# Keithley_2000_Omron_SCAN_V1_0.net
KiCad netlist of a schematic drawn in EasyEDA Pro
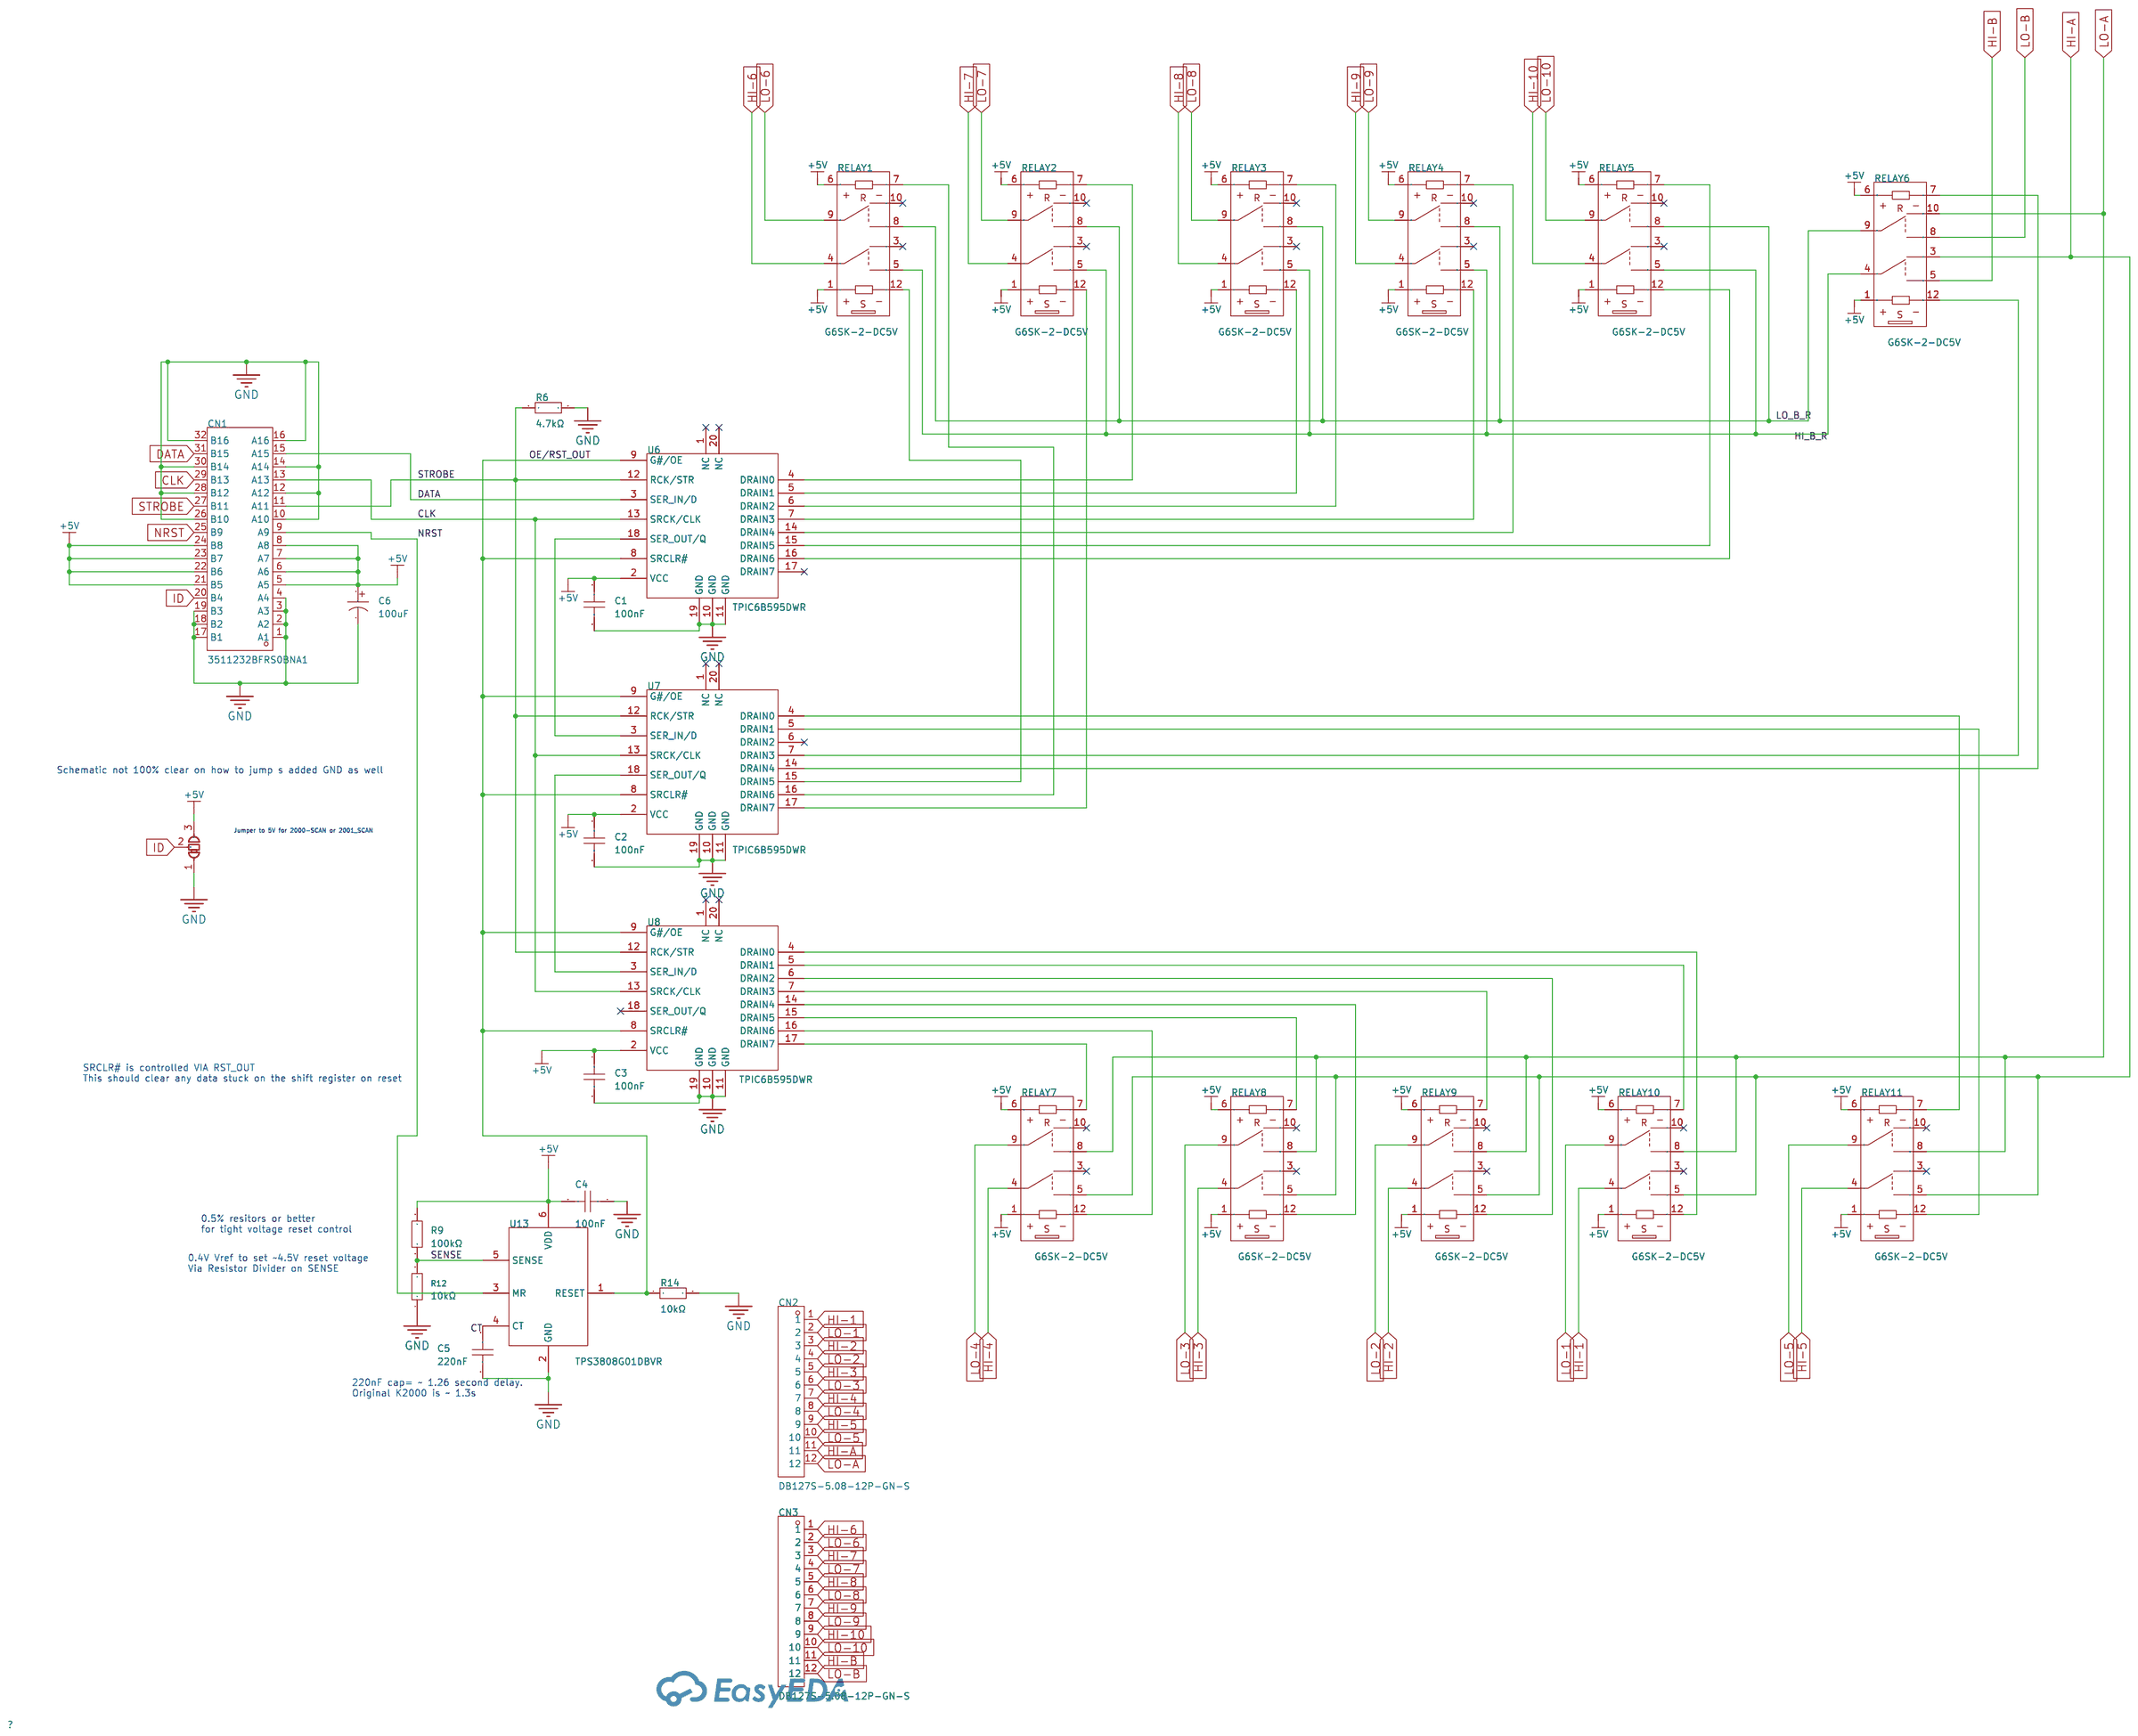
[diagram p0: schematic sheet]

(export (version "E")
  (design (tool "Eeschema 10.0.6"))
  (components
    (comp (ref "C1")
      (value "100nF")
      (description "Capacitance:100nF Tolerance:±10% Tolerance:±10% Voltage Rating:50V Temperature Coefficient:X7R")
      (fields
        (field (name "Manufacturer Part") "CL10B104KB8NNNC")
        (field (name "Manufacturer") "SAMSUNG(三星)")
      )
      (libsource (lib "easyedapro") (part "CAP"))
    )
    (comp (ref "C2")
      (value "100nF")
      (description "Capacitance:100nF Tolerance:±10% Tolerance:±10% Voltage Rating:50V Temperature Coefficient:X7R")
      (fields
        (field (name "Manufacturer Part") "CL10B104KB8NNNC")
        (field (name "Manufacturer") "SAMSUNG(三星)")
      )
      (libsource (lib "easyedapro") (part "CAP"))
    )
    (comp (ref "C3")
      (value "100nF")
      (description "Capacitance:100nF Tolerance:±10% Tolerance:±10% Voltage Rating:50V Temperature Coefficient:X7R")
      (fields
        (field (name "Manufacturer Part") "CL10B104KB8NNNC")
        (field (name "Manufacturer") "SAMSUNG(三星)")
      )
      (libsource (lib "easyedapro") (part "CAP"))
    )
    (comp (ref "C4")
      (value "100nF")
      (description "Capacitance:100nF Tolerance:±10% Tolerance:±10% Voltage Rating:50V Temperature Coefficient:X7R")
      (fields
        (field (name "Manufacturer Part") "CL10B104KB8NNNC")
        (field (name "Manufacturer") "SAMSUNG(三星)")
      )
      (libsource (lib "easyedapro") (part "CAP"))
    )
    (comp (ref "C5")
      (value "220nF")
      (description "Capacitance:220nF Tolerance:±10% Tolerance:±10% Voltage Rating:25V Temperature Coefficient:X7R")
      (fields
        (field (name "Manufacturer Part") "CL10B224KA8NNNC")
        (field (name "Manufacturer") "SAMSUNG(三星)")
      )
      (libsource (lib "easyedapro") (part "CAP"))
    )
    (comp (ref "C6")
      (value "100uF")
      (footprint "easyedapro:CAP-TH_BD8.0-P3.50-D0.6-FD")
      (fields (field (name "Manufacturer Part") "ERJ1HM101F12OT") (field (name "Manufacturer") "AISHI(艾华集团)"))
      (libsource (lib "easyedapro") (part "ERJ1HM101F12OT"))
    )
    (comp (ref "CN1")
      (value "3511232BFRS0BNA1")
      (footprint "easyedapro:CONN-TH_3511232BFRS0BNA1")
      (fields (field (name "Manufacturer") "JILN(锦凌)"))
      (libsource (lib "easyedapro") (part "3511232BFRS0BNA1"))
    )
    (comp (ref "CN2")
      (value "DB127S-5.08-12P-GN-S")
      (footprint "easyedapro:CONN-TH_12P-P5.08_DB127S-5.08-12P-GN-S")
      (fields (field (name "Manufacturer") "DORABO(地博电气)"))
      (libsource (lib "easyedapro") (part "DB127S-5.08-12P-GN-S"))
    )
    (comp (ref "CN3")
      (value "DB127S-5.08-12P-GN-S")
      (footprint "easyedapro:CONN-TH_12P-P5.08_DB127S-5.08-12P-GN-S")
      (fields (field (name "Manufacturer") "DORABO(地博电气)"))
      (libsource (lib "easyedapro") (part "DB127S-5.08-12P-GN-S"))
    )
    (comp (ref "JP1")
      (value "SolderJumper_3_Bridged12")
      (footprint "easyedapro:Jumper:SolderJumper-3_P1.3mm_Bridged12_Pad1.0x1.5mm_NumberLabels")
      (description "3-pole Solder Jumper, pins 1+2 closed/bridged")
      (libsource (lib "easyedapro") (part "Jumper_SolderJumper_3_Bridged12"))
    )
    (comp (ref "R6")
      (value "4.7kΩ")
      (fields (field (name "Manufacturer Part") "RC0603FR-074K7L") (field (name "Manufacturer") "YAGEO(国巨)"))
      (libsource (lib "easyedapro") (part "Res"))
    )
    (comp (ref "R9")
      (value "100kΩ")
      (footprint "easyedapro:R0603")
      (fields (field (name "Manufacturer Part") "AR03DTCX1003") (field (name "Manufacturer") "Viking(光颉)"))
      (libsource (lib "easyedapro") (part "AR03DTCX1003"))
    )
    (comp (ref "R12")
      (value "10kΩ")
      (footprint "easyedapro:R0603")
      (fields
        (field (name "Manufacturer Part") "0603WAD1002T5E")
        (field (name "Manufacturer") "UNI-ROYAL(厚声)")
      )
      (libsource (lib "easyedapro") (part "0603WAD1002T5E"))
    )
    (comp (ref "R14")
      (value "10kΩ")
      (fields (field (name "Manufacturer Part") "RC0603FR-0710KL") (field (name "Manufacturer") "YAGEO(国巨)"))
      (libsource (lib "easyedapro") (part "Res"))
    )
    (comp (ref "RELAY1")
      (value "G6SK-2-DC5V")
      (footprint "easyedapro:RELAY-TH_G6SK-2-XXX")
      (fields (field (name "Manufacturer") "OMRON(欧姆龙)"))
      (libsource (lib "easyedapro") (part "G6SK-2-DC5V"))
    )
    (comp (ref "RELAY2")
      (value "G6SK-2-DC5V")
      (footprint "easyedapro:RELAY-TH_G6SK-2-XXX")
      (fields (field (name "Manufacturer") "OMRON(欧姆龙)"))
      (libsource (lib "easyedapro") (part "G6SK-2-DC5V"))
    )
    (comp (ref "RELAY3")
      (value "G6SK-2-DC5V")
      (footprint "easyedapro:RELAY-TH_G6SK-2-XXX")
      (fields (field (name "Manufacturer") "OMRON(欧姆龙)"))
      (libsource (lib "easyedapro") (part "G6SK-2-DC5V"))
    )
    (comp (ref "RELAY4")
      (value "G6SK-2-DC5V")
      (footprint "easyedapro:RELAY-TH_G6SK-2-XXX")
      (fields (field (name "Manufacturer") "OMRON(欧姆龙)"))
      (libsource (lib "easyedapro") (part "G6SK-2-DC5V"))
    )
    (comp (ref "RELAY5")
      (value "G6SK-2-DC5V")
      (footprint "easyedapro:RELAY-TH_G6SK-2-XXX")
      (fields (field (name "Manufacturer") "OMRON(欧姆龙)"))
      (libsource (lib "easyedapro") (part "G6SK-2-DC5V"))
    )
    (comp (ref "RELAY6")
      (value "G6SK-2-DC5V")
      (footprint "easyedapro:RELAY-TH_G6SK-2-XXX")
      (fields (field (name "Manufacturer") "OMRON(欧姆龙)"))
      (libsource (lib "easyedapro") (part "G6SK-2-DC5V"))
    )
    (comp (ref "RELAY7")
      (value "G6SK-2-DC5V")
      (footprint "easyedapro:RELAY-TH_G6SK-2-XXX")
      (fields (field (name "Manufacturer") "OMRON(欧姆龙)"))
      (libsource (lib "easyedapro") (part "G6SK-2-DC5V"))
    )
    (comp (ref "RELAY8")
      (value "G6SK-2-DC5V")
      (footprint "easyedapro:RELAY-TH_G6SK-2-XXX")
      (fields (field (name "Manufacturer") "OMRON(欧姆龙)"))
      (libsource (lib "easyedapro") (part "G6SK-2-DC5V"))
    )
    (comp (ref "RELAY9")
      (value "G6SK-2-DC5V")
      (footprint "easyedapro:RELAY-TH_G6SK-2-XXX")
      (fields (field (name "Manufacturer") "OMRON(欧姆龙)"))
      (libsource (lib "easyedapro") (part "G6SK-2-DC5V"))
    )
    (comp (ref "RELAY10")
      (value "G6SK-2-DC5V")
      (footprint "easyedapro:RELAY-TH_G6SK-2-XXX")
      (fields (field (name "Manufacturer") "OMRON(欧姆龙)"))
      (libsource (lib "easyedapro") (part "G6SK-2-DC5V"))
    )
    (comp (ref "RELAY11")
      (value "G6SK-2-DC5V")
      (footprint "easyedapro:RELAY-TH_G6SK-2-XXX")
      (fields (field (name "Manufacturer") "OMRON(欧姆龙)"))
      (libsource (lib "easyedapro") (part "G6SK-2-DC5V"))
    )
    (comp (ref "U6")
      (value "TPIC6B595DWR")
      (footprint "easyedapro:SOIC-20_L13.0-W7.6-P1.27-LS10.3-BL")
      (fields (field (name "Manufacturer") "TI(德州仪器)"))
      (libsource (lib "easyedapro") (part "TPIC6B595DWR"))
    )
    (comp (ref "U7")
      (value "TPIC6B595DWR")
      (footprint "easyedapro:SOIC-20_L13.0-W7.6-P1.27-LS10.3-BL")
      (fields (field (name "Manufacturer") "TI(德州仪器)"))
      (libsource (lib "easyedapro") (part "TPIC6B595DWR"))
    )
    (comp (ref "U8")
      (value "TPIC6B595DWR")
      (footprint "easyedapro:SOIC-20_L13.0-W7.6-P1.27-LS10.3-BL")
      (fields (field (name "Manufacturer") "TI(德州仪器)"))
      (libsource (lib "easyedapro") (part "TPIC6B595DWR"))
    )
    (comp (ref "U13")
      (value "TPS3808G01DBVR")
      (footprint "easyedapro:SOT-23-6_L2.9-W1.6-P0.95-LS2.8-BR")
      (fields (field (name "Manufacturer") "TI(德州仪器)"))
      (libsource (lib "easyedapro") (part "TPS3808G01DBVR"))
    )
  )
  (nets
    (net (code "1") (name "+5V") (class "Default")
      (node (ref "C1") (pin "1") (pinfunction "1_1") (pintype "input"))
      (node (ref "C2") (pin "1") (pinfunction "1_1") (pintype "input"))
      (node (ref "C3") (pin "1") (pinfunction "1_1") (pintype "input"))
      (node (ref "C4") (pin "2") (pinfunction "2_2") (pintype "input"))
      (node (ref "C6") (pin "1") (pinfunction "1_1") (pintype "input"))
      (node (ref "CN1") (pin "21") (pinfunction "B5_21") (pintype "unspecified"))
      (node (ref "CN1") (pin "22") (pinfunction "B6_22") (pintype "unspecified"))
      (node (ref "CN1") (pin "23") (pinfunction "B7_23") (pintype "unspecified"))
      (node (ref "CN1") (pin "24") (pinfunction "B8_24") (pintype "unspecified"))
      (node (ref "CN1") (pin "5") (pinfunction "A5_5") (pintype "unspecified"))
      (node (ref "CN1") (pin "6") (pinfunction "A6_6") (pintype "unspecified"))
      (node (ref "CN1") (pin "7") (pinfunction "A7_7") (pintype "unspecified"))
      (node (ref "CN1") (pin "8") (pinfunction "A8_8") (pintype "unspecified"))
      (node (ref "JP1") (pin "3") (pinfunction "B_3") (pintype "unspecified"))
      (node (ref "R9") (pin "2") (pinfunction "2_2") (pintype "unspecified"))
      (node (ref "RELAY1") (pin "1") (pinfunction "1_1") (pintype "unspecified"))
      (node (ref "RELAY1") (pin "6") (pinfunction "6_6") (pintype "unspecified"))
      (node (ref "RELAY10") (pin "1") (pinfunction "1_1") (pintype "unspecified"))
      (node (ref "RELAY10") (pin "6") (pinfunction "6_6") (pintype "unspecified"))
      (node (ref "RELAY11") (pin "1") (pinfunction "1_1") (pintype "unspecified"))
      (node (ref "RELAY11") (pin "6") (pinfunction "6_6") (pintype "unspecified"))
      (node (ref "RELAY2") (pin "1") (pinfunction "1_1") (pintype "unspecified"))
      (node (ref "RELAY2") (pin "6") (pinfunction "6_6") (pintype "unspecified"))
      (node (ref "RELAY3") (pin "1") (pinfunction "1_1") (pintype "unspecified"))
      (node (ref "RELAY3") (pin "6") (pinfunction "6_6") (pintype "unspecified"))
      (node (ref "RELAY4") (pin "1") (pinfunction "1_1") (pintype "unspecified"))
      (node (ref "RELAY4") (pin "6") (pinfunction "6_6") (pintype "unspecified"))
      (node (ref "RELAY5") (pin "1") (pinfunction "1_1") (pintype "unspecified"))
      (node (ref "RELAY5") (pin "6") (pinfunction "6_6") (pintype "unspecified"))
      (node (ref "RELAY6") (pin "1") (pinfunction "1_1") (pintype "unspecified"))
      (node (ref "RELAY6") (pin "6") (pinfunction "6_6") (pintype "unspecified"))
      (node (ref "RELAY7") (pin "1") (pinfunction "1_1") (pintype "unspecified"))
      (node (ref "RELAY7") (pin "6") (pinfunction "6_6") (pintype "unspecified"))
      (node (ref "RELAY8") (pin "1") (pinfunction "1_1") (pintype "unspecified"))
      (node (ref "RELAY8") (pin "6") (pinfunction "6_6") (pintype "unspecified"))
      (node (ref "RELAY9") (pin "1") (pinfunction "1_1") (pintype "unspecified"))
      (node (ref "RELAY9") (pin "6") (pinfunction "6_6") (pintype "unspecified"))
      (node (ref "U13") (pin "6") (pinfunction "VDD_6") (pintype "unspecified"))
      (node (ref "U6") (pin "2") (pinfunction "VCC_2") (pintype "unspecified"))
      (node (ref "U7") (pin "2") (pinfunction "VCC_2") (pintype "unspecified"))
      (node (ref "U8") (pin "2") (pinfunction "VCC_2") (pintype "unspecified"))
    )
    (net (code "2") (name "/CT") (class "Default")
      (node (ref "C5") (pin "1") (pinfunction "1_1") (pintype "input"))
      (node (ref "U13") (pin "4") (pinfunction "CT_4") (pintype "unspecified"))
    )
    (net (code "3") (name "/HI_B_R") (class "Default")
      (node (ref "RELAY1") (pin "5") (pinfunction "5_5") (pintype "unspecified"))
      (node (ref "RELAY2") (pin "5") (pinfunction "5_5") (pintype "unspecified"))
      (node (ref "RELAY3") (pin "5") (pinfunction "5_5") (pintype "unspecified"))
      (node (ref "RELAY4") (pin "5") (pinfunction "5_5") (pintype "unspecified"))
      (node (ref "RELAY5") (pin "5") (pinfunction "5_5") (pintype "unspecified"))
      (node (ref "RELAY6") (pin "4") (pinfunction "4_4") (pintype "unspecified"))
    )
    (net (code "4") (name "/LO_B_R") (class "Default")
      (node (ref "RELAY1") (pin "8") (pinfunction "8_8") (pintype "unspecified"))
      (node (ref "RELAY2") (pin "8") (pinfunction "8_8") (pintype "unspecified"))
      (node (ref "RELAY3") (pin "8") (pinfunction "8_8") (pintype "unspecified"))
      (node (ref "RELAY4") (pin "8") (pinfunction "8_8") (pintype "unspecified"))
      (node (ref "RELAY5") (pin "8") (pinfunction "8_8") (pintype "unspecified"))
      (node (ref "RELAY6") (pin "9") (pinfunction "9_9") (pintype "unspecified"))
    )
    (net (code "5") (name "/OE{slash}RST_OUT") (class "Default")
      (node (ref "R14") (pin "1") (pinfunction "1_1") (pintype "input"))
      (node (ref "U13") (pin "1") (pinfunction "RESET_1") (pintype "unspecified"))
      (node (ref "U6") (pin "8") (pinfunction "SRCLR#_8") (pintype "unspecified"))
      (node (ref "U6") (pin "9") (pinfunction "G#/OE_9") (pintype "unspecified"))
      (node (ref "U7") (pin "8") (pinfunction "SRCLR#_8") (pintype "unspecified"))
      (node (ref "U7") (pin "9") (pinfunction "G#/OE_9") (pintype "unspecified"))
      (node (ref "U8") (pin "8") (pinfunction "SRCLR#_8") (pintype "unspecified"))
      (node (ref "U8") (pin "9") (pinfunction "G#/OE_9") (pintype "unspecified"))
    )
    (net (code "6") (name "/SENSE") (class "Default")
      (node (ref "R12") (pin "2") (pinfunction "2_2") (pintype "input"))
      (node (ref "R9") (pin "1") (pinfunction "1_1") (pintype "unspecified"))
      (node (ref "U13") (pin "5") (pinfunction "SENSE_5") (pintype "unspecified"))
    )
    (net (code "7") (name "CLK") (class "Default")
      (node (ref "CN1") (pin "13") (pinfunction "A13_13") (pintype "unspecified"))
      (node (ref "CN1") (pin "29") (pinfunction "B13_29") (pintype "unspecified"))
      (node (ref "U6") (pin "13") (pinfunction "SRCK/CLK_13") (pintype "unspecified"))
      (node (ref "U7") (pin "13") (pinfunction "SRCK/CLK_13") (pintype "unspecified"))
      (node (ref "U8") (pin "13") (pinfunction "SRCK/CLK_13") (pintype "unspecified"))
    )
    (net (code "8") (name "DATA") (class "Default")
      (node (ref "CN1") (pin "15") (pinfunction "A15_15") (pintype "unspecified"))
      (node (ref "CN1") (pin "31") (pinfunction "B15_31") (pintype "unspecified"))
      (node (ref "U6") (pin "3") (pinfunction "SER_IN/D_3") (pintype "unspecified"))
    )
    (net (code "9") (name "GND") (class "Default")
      (node (ref "C1") (pin "2") (pinfunction "2_2") (pintype "input"))
      (node (ref "C2") (pin "2") (pinfunction "2_2") (pintype "input"))
      (node (ref "C3") (pin "2") (pinfunction "2_2") (pintype "input"))
      (node (ref "C4") (pin "1") (pinfunction "1_1") (pintype "input"))
      (node (ref "C5") (pin "2") (pinfunction "2_2") (pintype "input"))
      (node (ref "C6") (pin "2") (pinfunction "2_2") (pintype "input"))
      (node (ref "CN1") (pin "1") (pinfunction "A1_1") (pintype "unspecified"))
      (node (ref "CN1") (pin "10") (pinfunction "A10_10") (pintype "unspecified"))
      (node (ref "CN1") (pin "12") (pinfunction "A12_12") (pintype "unspecified"))
      (node (ref "CN1") (pin "14") (pinfunction "A14_14") (pintype "unspecified"))
      (node (ref "CN1") (pin "16") (pinfunction "A16_16") (pintype "unspecified"))
      (node (ref "CN1") (pin "17") (pinfunction "B1_17") (pintype "unspecified"))
      (node (ref "CN1") (pin "18") (pinfunction "B2_18") (pintype "unspecified"))
      (node (ref "CN1") (pin "19") (pinfunction "B3_19") (pintype "unspecified"))
      (node (ref "CN1") (pin "2") (pinfunction "A2_2") (pintype "unspecified"))
      (node (ref "CN1") (pin "26") (pinfunction "B10_26") (pintype "unspecified"))
      (node (ref "CN1") (pin "28") (pinfunction "B12_28") (pintype "unspecified"))
      (node (ref "CN1") (pin "3") (pinfunction "A3_3") (pintype "unspecified"))
      (node (ref "CN1") (pin "30") (pinfunction "B14_30") (pintype "unspecified"))
      (node (ref "CN1") (pin "32") (pinfunction "B16_32") (pintype "unspecified"))
      (node (ref "CN1") (pin "4") (pinfunction "A4_4") (pintype "unspecified"))
      (node (ref "JP1") (pin "1") (pinfunction "A_1") (pintype "unspecified"))
      (node (ref "R12") (pin "1") (pinfunction "1_1") (pintype "input"))
      (node (ref "R14") (pin "2") (pinfunction "2_2") (pintype "input"))
      (node (ref "R6") (pin "2") (pinfunction "2_2") (pintype "input"))
      (node (ref "U13") (pin "2") (pinfunction "GND_2") (pintype "unspecified"))
      (node (ref "U6") (pin "10") (pinfunction "GND_10") (pintype "unspecified"))
      (node (ref "U6") (pin "11") (pinfunction "GND_11") (pintype "unspecified"))
      (node (ref "U6") (pin "19") (pinfunction "GND_19") (pintype "unspecified"))
      (node (ref "U7") (pin "10") (pinfunction "GND_10") (pintype "unspecified"))
      (node (ref "U7") (pin "11") (pinfunction "GND_11") (pintype "unspecified"))
      (node (ref "U7") (pin "19") (pinfunction "GND_19") (pintype "unspecified"))
      (node (ref "U8") (pin "10") (pinfunction "GND_10") (pintype "unspecified"))
      (node (ref "U8") (pin "11") (pinfunction "GND_11") (pintype "unspecified"))
      (node (ref "U8") (pin "19") (pinfunction "GND_19") (pintype "unspecified"))
    )
    (net (code "10") (name "HI-1") (class "Default")
      (node (ref "CN2") (pin "1") (pinfunction "1_1") (pintype "unspecified"))
      (node (ref "RELAY10") (pin "4") (pinfunction "4_4") (pintype "unspecified"))
    )
    (net (code "11") (name "HI-2") (class "Default")
      (node (ref "CN2") (pin "3") (pinfunction "3_3") (pintype "unspecified"))
      (node (ref "RELAY9") (pin "4") (pinfunction "4_4") (pintype "unspecified"))
    )
    (net (code "12") (name "HI-3") (class "Default")
      (node (ref "CN2") (pin "5") (pinfunction "5_5") (pintype "unspecified"))
      (node (ref "RELAY8") (pin "4") (pinfunction "4_4") (pintype "unspecified"))
    )
    (net (code "13") (name "HI-4") (class "Default")
      (node (ref "CN2") (pin "7") (pinfunction "7_7") (pintype "unspecified"))
      (node (ref "RELAY7") (pin "4") (pinfunction "4_4") (pintype "unspecified"))
    )
    (net (code "14") (name "HI-5") (class "Default")
      (node (ref "CN2") (pin "9") (pinfunction "9_9") (pintype "unspecified"))
      (node (ref "RELAY11") (pin "4") (pinfunction "4_4") (pintype "unspecified"))
    )
    (net (code "15") (name "HI-6") (class "Default")
      (node (ref "CN3") (pin "1") (pinfunction "1_1") (pintype "unspecified"))
      (node (ref "RELAY1") (pin "4") (pinfunction "4_4") (pintype "unspecified"))
    )
    (net (code "16") (name "HI-7") (class "Default")
      (node (ref "CN3") (pin "3") (pinfunction "3_3") (pintype "unspecified"))
      (node (ref "RELAY2") (pin "4") (pinfunction "4_4") (pintype "unspecified"))
    )
    (net (code "17") (name "HI-8") (class "Default")
      (node (ref "CN3") (pin "5") (pinfunction "5_5") (pintype "unspecified"))
      (node (ref "RELAY3") (pin "4") (pinfunction "4_4") (pintype "unspecified"))
    )
    (net (code "18") (name "HI-9") (class "Default")
      (node (ref "CN3") (pin "7") (pinfunction "7_7") (pintype "unspecified"))
      (node (ref "RELAY4") (pin "4") (pinfunction "4_4") (pintype "unspecified"))
    )
    (net (code "19") (name "HI-10") (class "Default")
      (node (ref "CN3") (pin "9") (pinfunction "9_9") (pintype "unspecified"))
      (node (ref "RELAY5") (pin "4") (pinfunction "4_4") (pintype "unspecified"))
    )
    (net (code "20") (name "HI-A") (class "Default")
      (node (ref "CN2") (pin "11") (pinfunction "11_11") (pintype "unspecified"))
      (node (ref "RELAY10") (pin "5") (pinfunction "5_5") (pintype "unspecified"))
      (node (ref "RELAY11") (pin "5") (pinfunction "5_5") (pintype "unspecified"))
      (node (ref "RELAY6") (pin "3") (pinfunction "3_3") (pintype "unspecified"))
      (node (ref "RELAY7") (pin "5") (pinfunction "5_5") (pintype "unspecified"))
      (node (ref "RELAY8") (pin "5") (pinfunction "5_5") (pintype "unspecified"))
      (node (ref "RELAY9") (pin "5") (pinfunction "5_5") (pintype "unspecified"))
    )
    (net (code "21") (name "HI-B") (class "Default")
      (node (ref "CN3") (pin "11") (pinfunction "11_11") (pintype "unspecified"))
      (node (ref "RELAY6") (pin "5") (pinfunction "5_5") (pintype "unspecified"))
    )
    (net (code "22") (name "ID") (class "Default")
      (node (ref "CN1") (pin "20") (pinfunction "B4_20") (pintype "unspecified"))
      (node (ref "JP1") (pin "2") (pinfunction "C_2") (pintype "unspecified"))
    )
    (net (code "23") (name "LO-1") (class "Default")
      (node (ref "CN2") (pin "2") (pinfunction "2_2") (pintype "unspecified"))
      (node (ref "RELAY10") (pin "9") (pinfunction "9_9") (pintype "unspecified"))
    )
    (net (code "24") (name "LO-2") (class "Default")
      (node (ref "CN2") (pin "4") (pinfunction "4_4") (pintype "unspecified"))
      (node (ref "RELAY9") (pin "9") (pinfunction "9_9") (pintype "unspecified"))
    )
    (net (code "25") (name "LO-3") (class "Default")
      (node (ref "CN2") (pin "6") (pinfunction "6_6") (pintype "unspecified"))
      (node (ref "RELAY8") (pin "9") (pinfunction "9_9") (pintype "unspecified"))
    )
    (net (code "26") (name "LO-4") (class "Default")
      (node (ref "CN2") (pin "8") (pinfunction "8_8") (pintype "unspecified"))
      (node (ref "RELAY7") (pin "9") (pinfunction "9_9") (pintype "unspecified"))
    )
    (net (code "27") (name "LO-5") (class "Default")
      (node (ref "CN2") (pin "10") (pinfunction "10_10") (pintype "unspecified"))
      (node (ref "RELAY11") (pin "9") (pinfunction "9_9") (pintype "unspecified"))
    )
    (net (code "28") (name "LO-6") (class "Default")
      (node (ref "CN3") (pin "2") (pinfunction "2_2") (pintype "unspecified"))
      (node (ref "RELAY1") (pin "9") (pinfunction "9_9") (pintype "unspecified"))
    )
    (net (code "29") (name "LO-7") (class "Default")
      (node (ref "CN3") (pin "4") (pinfunction "4_4") (pintype "unspecified"))
      (node (ref "RELAY2") (pin "9") (pinfunction "9_9") (pintype "unspecified"))
    )
    (net (code "30") (name "LO-8") (class "Default")
      (node (ref "CN3") (pin "6") (pinfunction "6_6") (pintype "unspecified"))
      (node (ref "RELAY3") (pin "9") (pinfunction "9_9") (pintype "unspecified"))
    )
    (net (code "31") (name "LO-9") (class "Default")
      (node (ref "CN3") (pin "8") (pinfunction "8_8") (pintype "unspecified"))
      (node (ref "RELAY4") (pin "9") (pinfunction "9_9") (pintype "unspecified"))
    )
    (net (code "32") (name "LO-10") (class "Default")
      (node (ref "CN3") (pin "10") (pinfunction "10_10") (pintype "unspecified"))
      (node (ref "RELAY5") (pin "9") (pinfunction "9_9") (pintype "unspecified"))
    )
    (net (code "33") (name "LO-A") (class "Default")
      (node (ref "CN2") (pin "12") (pinfunction "12_12") (pintype "unspecified"))
      (node (ref "RELAY10") (pin "8") (pinfunction "8_8") (pintype "unspecified"))
      (node (ref "RELAY11") (pin "8") (pinfunction "8_8") (pintype "unspecified"))
      (node (ref "RELAY6") (pin "10") (pinfunction "10_10") (pintype "unspecified"))
      (node (ref "RELAY7") (pin "8") (pinfunction "8_8") (pintype "unspecified"))
      (node (ref "RELAY8") (pin "8") (pinfunction "8_8") (pintype "unspecified"))
      (node (ref "RELAY9") (pin "8") (pinfunction "8_8") (pintype "unspecified"))
    )
    (net (code "34") (name "LO-B") (class "Default")
      (node (ref "CN3") (pin "12") (pinfunction "12_12") (pintype "unspecified"))
      (node (ref "RELAY6") (pin "8") (pinfunction "8_8") (pintype "unspecified"))
    )
    (net (code "35") (name "NRST") (class "Default")
      (node (ref "CN1") (pin "25") (pinfunction "B9_25") (pintype "unspecified"))
      (node (ref "CN1") (pin "9") (pinfunction "A9_9") (pintype "unspecified"))
      (node (ref "U13") (pin "3") (pinfunction "MR_3") (pintype "unspecified"))
    )
    (net (code "36") (name "Net-(U6-DRAIN0)") (class "Default")
      (node (ref "RELAY2") (pin "7") (pinfunction "7_7") (pintype "unspecified"))
      (node (ref "U6") (pin "4") (pinfunction "DRAIN0_4") (pintype "unspecified"))
    )
    (net (code "37") (name "Net-(U6-DRAIN1)") (class "Default")
      (node (ref "RELAY3") (pin "12") (pinfunction "12_12") (pintype "unspecified"))
      (node (ref "U6") (pin "5") (pinfunction "DRAIN1_5") (pintype "unspecified"))
    )
    (net (code "38") (name "Net-(U6-DRAIN2)") (class "Default")
      (node (ref "RELAY3") (pin "7") (pinfunction "7_7") (pintype "unspecified"))
      (node (ref "U6") (pin "6") (pinfunction "DRAIN2_6") (pintype "unspecified"))
    )
    (net (code "39") (name "Net-(U6-DRAIN3)") (class "Default")
      (node (ref "RELAY4") (pin "12") (pinfunction "12_12") (pintype "unspecified"))
      (node (ref "U6") (pin "7") (pinfunction "DRAIN3_7") (pintype "unspecified"))
    )
    (net (code "40") (name "Net-(U6-DRAIN4)") (class "Default")
      (node (ref "RELAY4") (pin "7") (pinfunction "7_7") (pintype "unspecified"))
      (node (ref "U6") (pin "14") (pinfunction "DRAIN4_14") (pintype "unspecified"))
    )
    (net (code "41") (name "Net-(U6-DRAIN5)") (class "Default")
      (node (ref "RELAY5") (pin "7") (pinfunction "7_7") (pintype "unspecified"))
      (node (ref "U6") (pin "15") (pinfunction "DRAIN5_15") (pintype "unspecified"))
    )
    (net (code "42") (name "Net-(U6-DRAIN6)") (class "Default")
      (node (ref "RELAY5") (pin "12") (pinfunction "12_12") (pintype "unspecified"))
      (node (ref "U6") (pin "16") (pinfunction "DRAIN6_16") (pintype "unspecified"))
    )
    (net (code "43") (name "Net-(U6-SER_OUT{slash}Q)") (class "Default")
      (node (ref "U6") (pin "18") (pinfunction "SER_OUT/Q_18") (pintype "unspecified"))
      (node (ref "U7") (pin "3") (pinfunction "SER_IN/D_3") (pintype "unspecified"))
    )
    (net (code "44") (name "Net-(U7-DRAIN0)") (class "Default")
      (node (ref "RELAY11") (pin "7") (pinfunction "7_7") (pintype "unspecified"))
      (node (ref "U7") (pin "4") (pinfunction "DRAIN0_4") (pintype "unspecified"))
    )
    (net (code "45") (name "Net-(U7-DRAIN1)") (class "Default")
      (node (ref "RELAY11") (pin "12") (pinfunction "12_12") (pintype "unspecified"))
      (node (ref "U7") (pin "5") (pinfunction "DRAIN1_5") (pintype "unspecified"))
    )
    (net (code "46") (name "Net-(U7-DRAIN3)") (class "Default")
      (node (ref "RELAY6") (pin "12") (pinfunction "12_12") (pintype "unspecified"))
      (node (ref "U7") (pin "7") (pinfunction "DRAIN3_7") (pintype "unspecified"))
    )
    (net (code "47") (name "Net-(U7-DRAIN4)") (class "Default")
      (node (ref "RELAY6") (pin "7") (pinfunction "7_7") (pintype "unspecified"))
      (node (ref "U7") (pin "14") (pinfunction "DRAIN4_14") (pintype "unspecified"))
    )
    (net (code "48") (name "Net-(U7-DRAIN5)") (class "Default")
      (node (ref "RELAY1") (pin "12") (pinfunction "12_12") (pintype "unspecified"))
      (node (ref "U7") (pin "15") (pinfunction "DRAIN5_15") (pintype "unspecified"))
    )
    (net (code "49") (name "Net-(U7-DRAIN6)") (class "Default")
      (node (ref "RELAY1") (pin "7") (pinfunction "7_7") (pintype "unspecified"))
      (node (ref "U7") (pin "16") (pinfunction "DRAIN6_16") (pintype "unspecified"))
    )
    (net (code "50") (name "Net-(U7-DRAIN7)") (class "Default")
      (node (ref "RELAY2") (pin "12") (pinfunction "12_12") (pintype "unspecified"))
      (node (ref "U7") (pin "17") (pinfunction "DRAIN7_17") (pintype "unspecified"))
    )
    (net (code "51") (name "Net-(U7-SER_OUT{slash}Q)") (class "Default")
      (node (ref "U7") (pin "18") (pinfunction "SER_OUT/Q_18") (pintype "unspecified"))
      (node (ref "U8") (pin "3") (pinfunction "SER_IN/D_3") (pintype "unspecified"))
    )
    (net (code "52") (name "Net-(U8-DRAIN0)") (class "Default")
      (node (ref "RELAY10") (pin "12") (pinfunction "12_12") (pintype "unspecified"))
      (node (ref "U8") (pin "4") (pinfunction "DRAIN0_4") (pintype "unspecified"))
    )
    (net (code "53") (name "Net-(U8-DRAIN1)") (class "Default")
      (node (ref "RELAY10") (pin "7") (pinfunction "7_7") (pintype "unspecified"))
      (node (ref "U8") (pin "5") (pinfunction "DRAIN1_5") (pintype "unspecified"))
    )
    (net (code "54") (name "Net-(U8-DRAIN2)") (class "Default")
      (node (ref "RELAY9") (pin "12") (pinfunction "12_12") (pintype "unspecified"))
      (node (ref "U8") (pin "6") (pinfunction "DRAIN2_6") (pintype "unspecified"))
    )
    (net (code "55") (name "Net-(U8-DRAIN3)") (class "Default")
      (node (ref "RELAY9") (pin "7") (pinfunction "7_7") (pintype "unspecified"))
      (node (ref "U8") (pin "7") (pinfunction "DRAIN3_7") (pintype "unspecified"))
    )
    (net (code "56") (name "Net-(U8-DRAIN4)") (class "Default")
      (node (ref "RELAY8") (pin "12") (pinfunction "12_12") (pintype "unspecified"))
      (node (ref "U8") (pin "14") (pinfunction "DRAIN4_14") (pintype "unspecified"))
    )
    (net (code "57") (name "Net-(U8-DRAIN5)") (class "Default")
      (node (ref "RELAY8") (pin "7") (pinfunction "7_7") (pintype "unspecified"))
      (node (ref "U8") (pin "15") (pinfunction "DRAIN5_15") (pintype "unspecified"))
    )
    (net (code "58") (name "Net-(U8-DRAIN6)") (class "Default")
      (node (ref "RELAY7") (pin "12") (pinfunction "12_12") (pintype "unspecified"))
      (node (ref "U8") (pin "16") (pinfunction "DRAIN6_16") (pintype "unspecified"))
    )
    (net (code "59") (name "Net-(U8-DRAIN7)") (class "Default")
      (node (ref "RELAY7") (pin "7") (pinfunction "7_7") (pintype "unspecified"))
      (node (ref "U8") (pin "17") (pinfunction "DRAIN7_17") (pintype "unspecified"))
    )
    (net (code "60") (name "STROBE") (class "Default")
      (node (ref "CN1") (pin "11") (pinfunction "A11_11") (pintype "unspecified"))
      (node (ref "CN1") (pin "27") (pinfunction "B11_27") (pintype "unspecified"))
      (node (ref "R6") (pin "1") (pinfunction "1_1") (pintype "input"))
      (node (ref "U6") (pin "12") (pinfunction "RCK/STR_12") (pintype "unspecified"))
      (node (ref "U7") (pin "12") (pinfunction "RCK/STR_12") (pintype "unspecified"))
      (node (ref "U8") (pin "12") (pinfunction "RCK/STR_12") (pintype "unspecified"))
    )
    (net (code "61") (name "unconnected-(RELAY1-Pad3)") (class "Default")
      (node (ref "RELAY1") (pin "3") (pinfunction "3_3") (pintype "unspecified+no_connect"))
    )
    (net (code "62") (name "unconnected-(RELAY1-Pad10)") (class "Default")
      (node (ref "RELAY1") (pin "10") (pinfunction "10_10") (pintype "unspecified+no_connect"))
    )
    (net (code "63") (name "unconnected-(RELAY2-Pad3)") (class "Default")
      (node (ref "RELAY2") (pin "3") (pinfunction "3_3") (pintype "unspecified+no_connect"))
    )
    (net (code "64") (name "unconnected-(RELAY2-Pad10)") (class "Default")
      (node (ref "RELAY2") (pin "10") (pinfunction "10_10") (pintype "unspecified+no_connect"))
    )
    (net (code "65") (name "unconnected-(RELAY3-Pad3)") (class "Default")
      (node (ref "RELAY3") (pin "3") (pinfunction "3_3") (pintype "unspecified+no_connect"))
    )
    (net (code "66") (name "unconnected-(RELAY3-Pad10)") (class "Default")
      (node (ref "RELAY3") (pin "10") (pinfunction "10_10") (pintype "unspecified+no_connect"))
    )
    (net (code "67") (name "unconnected-(RELAY4-Pad3)") (class "Default")
      (node (ref "RELAY4") (pin "3") (pinfunction "3_3") (pintype "unspecified+no_connect"))
    )
    (net (code "68") (name "unconnected-(RELAY4-Pad10)") (class "Default")
      (node (ref "RELAY4") (pin "10") (pinfunction "10_10") (pintype "unspecified+no_connect"))
    )
    (net (code "69") (name "unconnected-(RELAY5-Pad3)") (class "Default")
      (node (ref "RELAY5") (pin "3") (pinfunction "3_3") (pintype "unspecified+no_connect"))
    )
    (net (code "70") (name "unconnected-(RELAY5-Pad10)") (class "Default")
      (node (ref "RELAY5") (pin "10") (pinfunction "10_10") (pintype "unspecified+no_connect"))
    )
    (net (code "71") (name "unconnected-(RELAY7-Pad3)") (class "Default")
      (node (ref "RELAY7") (pin "3") (pinfunction "3_3") (pintype "unspecified+no_connect"))
    )
    (net (code "72") (name "unconnected-(RELAY7-Pad10)") (class "Default")
      (node (ref "RELAY7") (pin "10") (pinfunction "10_10") (pintype "unspecified+no_connect"))
    )
    (net (code "73") (name "unconnected-(RELAY8-Pad3)") (class "Default")
      (node (ref "RELAY8") (pin "3") (pinfunction "3_3") (pintype "unspecified+no_connect"))
    )
    (net (code "74") (name "unconnected-(RELAY8-Pad10)") (class "Default")
      (node (ref "RELAY8") (pin "10") (pinfunction "10_10") (pintype "unspecified+no_connect"))
    )
    (net (code "75") (name "unconnected-(RELAY9-Pad3)") (class "Default")
      (node (ref "RELAY9") (pin "3") (pinfunction "3_3") (pintype "unspecified+no_connect"))
    )
    (net (code "76") (name "unconnected-(RELAY9-Pad10)") (class "Default")
      (node (ref "RELAY9") (pin "10") (pinfunction "10_10") (pintype "unspecified+no_connect"))
    )
    (net (code "77") (name "unconnected-(RELAY10-Pad3)") (class "Default")
      (node (ref "RELAY10") (pin "3") (pinfunction "3_3") (pintype "unspecified+no_connect"))
    )
    (net (code "78") (name "unconnected-(RELAY10-Pad10)") (class "Default")
      (node (ref "RELAY10") (pin "10") (pinfunction "10_10") (pintype "unspecified+no_connect"))
    )
    (net (code "79") (name "unconnected-(RELAY11-Pad3)") (class "Default")
      (node (ref "RELAY11") (pin "3") (pinfunction "3_3") (pintype "unspecified+no_connect"))
    )
    (net (code "80") (name "unconnected-(RELAY11-Pad10)") (class "Default")
      (node (ref "RELAY11") (pin "10") (pinfunction "10_10") (pintype "unspecified+no_connect"))
    )
    (net (code "81") (name "unconnected-(U6-DRAIN7-Pad17)") (class "Default")
      (node (ref "U6") (pin "17") (pinfunction "DRAIN7_17") (pintype "unspecified+no_connect"))
    )
    (net (code "82") (name "unconnected-(U6-NC-Pad1)") (class "Default")
      (node (ref "U6") (pin "1") (pinfunction "NC_1") (pintype "unspecified+no_connect"))
    )
    (net (code "83") (name "unconnected-(U6-NC-Pad20)") (class "Default")
      (node (ref "U6") (pin "20") (pinfunction "NC_20") (pintype "unspecified+no_connect"))
    )
    (net (code "84") (name "unconnected-(U7-DRAIN2-Pad6)") (class "Default")
      (node (ref "U7") (pin "6") (pinfunction "DRAIN2_6") (pintype "unspecified+no_connect"))
    )
    (net (code "85") (name "unconnected-(U7-NC-Pad1)") (class "Default")
      (node (ref "U7") (pin "1") (pinfunction "NC_1") (pintype "unspecified+no_connect"))
    )
    (net (code "86") (name "unconnected-(U7-NC-Pad20)") (class "Default")
      (node (ref "U7") (pin "20") (pinfunction "NC_20") (pintype "unspecified+no_connect"))
    )
    (net (code "87") (name "unconnected-(U8-NC-Pad1)") (class "Default")
      (node (ref "U8") (pin "1") (pinfunction "NC_1") (pintype "unspecified+no_connect"))
    )
    (net (code "88") (name "unconnected-(U8-NC-Pad20)") (class "Default")
      (node (ref "U8") (pin "20") (pinfunction "NC_20") (pintype "unspecified+no_connect"))
    )
    (net (code "89") (name "unconnected-(U8-SER_OUT{slash}Q-Pad18)") (class "Default")
      (node (ref "U8") (pin "18") (pinfunction "SER_OUT/Q_18") (pintype "unspecified+no_connect"))
    )
  )
)
